# untitled.net
KiCad netlist of a schematic drawn in EAGLE
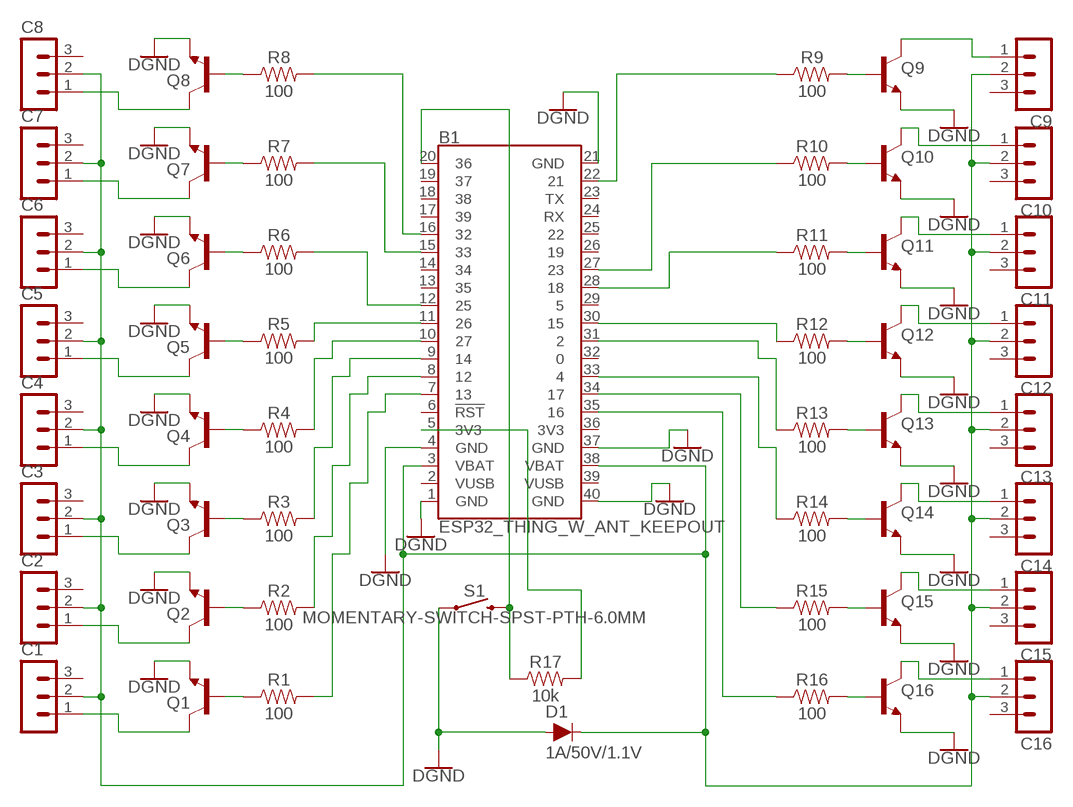
[diagram p0: schematic, sheet 1]

(export (version "E")
  (design (tool "Eeschema 10.0.6"))
  (components
    (comp (ref "B1")
      (value "ESP32_THING_W_ANT_KEEPOUT")
      (footprint "eagle-import:ESP32_THING")
      (libsource (lib "eagle-import") (part "ESP32_THING_W_ANT_KEEPOUT"))
    )
    (comp (ref "C1")
      (value "MA03-1")
      (footprint "eagle-import:MA03-1")
      (libsource (lib "eagle-import") (part "MA03-1"))
    )
    (comp (ref "C2")
      (value "MA03-1")
      (footprint "eagle-import:MA03-1")
      (libsource (lib "eagle-import") (part "MA03-1"))
    )
    (comp (ref "C3")
      (value "MA03-1")
      (footprint "eagle-import:MA03-1")
      (libsource (lib "eagle-import") (part "MA03-1"))
    )
    (comp (ref "C4")
      (value "MA03-1")
      (footprint "eagle-import:MA03-1")
      (libsource (lib "eagle-import") (part "MA03-1"))
    )
    (comp (ref "C5")
      (value "MA03-1")
      (footprint "eagle-import:MA03-1")
      (libsource (lib "eagle-import") (part "MA03-1"))
    )
    (comp (ref "C6")
      (value "MA03-1")
      (footprint "eagle-import:MA03-1")
      (libsource (lib "eagle-import") (part "MA03-1"))
    )
    (comp (ref "C7")
      (value "MA03-1")
      (footprint "eagle-import:MA03-1")
      (libsource (lib "eagle-import") (part "MA03-1"))
    )
    (comp (ref "C8")
      (value "MA03-1")
      (footprint "eagle-import:MA03-1")
      (libsource (lib "eagle-import") (part "MA03-1"))
    )
    (comp (ref "C9")
      (value "MA03-1")
      (footprint "eagle-import:MA03-1")
      (libsource (lib "eagle-import") (part "MA03-1"))
    )
    (comp (ref "C10")
      (value "MA03-1")
      (footprint "eagle-import:MA03-1")
      (libsource (lib "eagle-import") (part "MA03-1"))
    )
    (comp (ref "C11")
      (value "MA03-1")
      (footprint "eagle-import:MA03-1")
      (libsource (lib "eagle-import") (part "MA03-1"))
    )
    (comp (ref "C12")
      (value "MA03-1")
      (footprint "eagle-import:MA03-1")
      (libsource (lib "eagle-import") (part "MA03-1"))
    )
    (comp (ref "C13")
      (value "MA03-1")
      (footprint "eagle-import:MA03-1")
      (libsource (lib "eagle-import") (part "MA03-1"))
    )
    (comp (ref "C14")
      (value "MA03-1")
      (footprint "eagle-import:MA03-1")
      (libsource (lib "eagle-import") (part "MA03-1"))
    )
    (comp (ref "C15")
      (value "MA03-1")
      (footprint "eagle-import:MA03-1")
      (libsource (lib "eagle-import") (part "MA03-1"))
    )
    (comp (ref "C16")
      (value "MA03-1")
      (footprint "eagle-import:MA03-1")
      (libsource (lib "eagle-import") (part "MA03-1"))
    )
    (comp (ref "D1")
      (value "1A/50V/1.1V")
      (footprint "eagle-import:DIODE-1N4001")
      (libsource (lib "eagle-import") (part "DIODE-PTH"))
    )
    (comp (ref "Q1")
      (value "600mA/40V")
      (footprint "eagle-import:TO92-EBC")
      (libsource (lib "eagle-import") (part "-NPN-TO92-EBC2N2222"))
    )
    (comp (ref "Q2")
      (value "600mA/40V")
      (footprint "eagle-import:TO92-EBC")
      (libsource (lib "eagle-import") (part "-NPN-TO92-EBC2N2222"))
    )
    (comp (ref "Q3")
      (value "600mA/40V")
      (footprint "eagle-import:TO92-EBC")
      (libsource (lib "eagle-import") (part "-NPN-TO92-EBC2N2222"))
    )
    (comp (ref "Q4")
      (value "600mA/40V")
      (footprint "eagle-import:TO92-EBC")
      (libsource (lib "eagle-import") (part "-NPN-TO92-EBC2N2222"))
    )
    (comp (ref "Q5")
      (value "600mA/40V")
      (footprint "eagle-import:TO92-EBC")
      (libsource (lib "eagle-import") (part "-NPN-TO92-EBC2N2222"))
    )
    (comp (ref "Q6")
      (value "600mA/40V")
      (footprint "eagle-import:TO92-EBC")
      (libsource (lib "eagle-import") (part "-NPN-TO92-EBC2N2222"))
    )
    (comp (ref "Q7")
      (value "600mA/40V")
      (footprint "eagle-import:TO92-EBC")
      (libsource (lib "eagle-import") (part "-NPN-TO92-EBC2N2222"))
    )
    (comp (ref "Q8")
      (value "600mA/40V")
      (footprint "eagle-import:TO92-EBC")
      (libsource (lib "eagle-import") (part "-NPN-TO92-EBC2N2222"))
    )
    (comp (ref "Q9")
      (value "600mA/40V")
      (footprint "eagle-import:TO92-EBC")
      (libsource (lib "eagle-import") (part "-NPN-TO92-EBC2N2222"))
    )
    (comp (ref "Q10")
      (value "600mA/40V")
      (footprint "eagle-import:TO92-EBC")
      (libsource (lib "eagle-import") (part "-NPN-TO92-EBC2N2222"))
    )
    (comp (ref "Q11")
      (value "600mA/40V")
      (footprint "eagle-import:TO92-EBC")
      (libsource (lib "eagle-import") (part "-NPN-TO92-EBC2N2222"))
    )
    (comp (ref "Q12")
      (value "600mA/40V")
      (footprint "eagle-import:TO92-EBC")
      (libsource (lib "eagle-import") (part "-NPN-TO92-EBC2N2222"))
    )
    (comp (ref "Q13")
      (value "600mA/40V")
      (footprint "eagle-import:TO92-EBC")
      (libsource (lib "eagle-import") (part "-NPN-TO92-EBC2N2222"))
    )
    (comp (ref "Q14")
      (value "600mA/40V")
      (footprint "eagle-import:TO92-EBC")
      (libsource (lib "eagle-import") (part "-NPN-TO92-EBC2N2222"))
    )
    (comp (ref "Q15")
      (value "600mA/40V")
      (footprint "eagle-import:TO92-EBC")
      (libsource (lib "eagle-import") (part "-NPN-TO92-EBC2N2222"))
    )
    (comp (ref "Q16")
      (value "600mA/40V")
      (footprint "eagle-import:TO92-EBC")
      (libsource (lib "eagle-import") (part "-NPN-TO92-EBC2N2222"))
    )
    (comp (ref "R1")
      (value "100")
      (footprint "eagle-import:AXIAL-0.1")
      (libsource (lib "eagle-import") (part "100OHM-VERT-1/4W-1%"))
    )
    (comp (ref "R2")
      (value "100")
      (footprint "eagle-import:AXIAL-0.1")
      (libsource (lib "eagle-import") (part "100OHM-VERT-1/4W-1%"))
    )
    (comp (ref "R3")
      (value "100")
      (footprint "eagle-import:AXIAL-0.1")
      (libsource (lib "eagle-import") (part "100OHM-VERT-1/4W-1%"))
    )
    (comp (ref "R4")
      (value "100")
      (footprint "eagle-import:AXIAL-0.1")
      (libsource (lib "eagle-import") (part "100OHM-VERT-1/4W-1%"))
    )
    (comp (ref "R5")
      (value "100")
      (footprint "eagle-import:AXIAL-0.1")
      (libsource (lib "eagle-import") (part "100OHM-VERT-1/4W-1%"))
    )
    (comp (ref "R6")
      (value "100")
      (footprint "eagle-import:AXIAL-0.1")
      (libsource (lib "eagle-import") (part "100OHM-VERT-1/4W-1%"))
    )
    (comp (ref "R7")
      (value "100")
      (footprint "eagle-import:AXIAL-0.1")
      (libsource (lib "eagle-import") (part "100OHM-VERT-1/4W-1%"))
    )
    (comp (ref "R8")
      (value "100")
      (footprint "eagle-import:AXIAL-0.1")
      (libsource (lib "eagle-import") (part "100OHM-VERT-1/4W-1%"))
    )
    (comp (ref "R9")
      (value "100")
      (footprint "eagle-import:AXIAL-0.1")
      (libsource (lib "eagle-import") (part "100OHM-VERT-1/4W-1%"))
    )
    (comp (ref "R10")
      (value "100")
      (footprint "eagle-import:AXIAL-0.1")
      (libsource (lib "eagle-import") (part "100OHM-VERT-1/4W-1%"))
    )
    (comp (ref "R11")
      (value "100")
      (footprint "eagle-import:AXIAL-0.1")
      (libsource (lib "eagle-import") (part "100OHM-VERT-1/4W-1%"))
    )
    (comp (ref "R12")
      (value "100")
      (footprint "eagle-import:AXIAL-0.1")
      (libsource (lib "eagle-import") (part "100OHM-VERT-1/4W-1%"))
    )
    (comp (ref "R13")
      (value "100")
      (footprint "eagle-import:AXIAL-0.1")
      (libsource (lib "eagle-import") (part "100OHM-VERT-1/4W-1%"))
    )
    (comp (ref "R14")
      (value "100")
      (footprint "eagle-import:AXIAL-0.1")
      (libsource (lib "eagle-import") (part "100OHM-VERT-1/4W-1%"))
    )
    (comp (ref "R15")
      (value "100")
      (footprint "eagle-import:AXIAL-0.1")
      (libsource (lib "eagle-import") (part "100OHM-VERT-1/4W-1%"))
    )
    (comp (ref "R16")
      (value "100")
      (footprint "eagle-import:AXIAL-0.1")
      (libsource (lib "eagle-import") (part "100OHM-VERT-1/4W-1%"))
    )
    (comp (ref "R17")
      (value "10k")
      (footprint "eagle-import:AXIAL-0.1")
      (libsource (lib "eagle-import") (part "10KOHM-VERT-1/4W-5%"))
    )
    (comp (ref "S1")
      (value "MOMENTARY-SWITCH-SPST-PTH-6.0MM")
      (footprint "eagle-import:TACTILE_SWITCH_PTH_6.0MM")
      (libsource (lib "eagle-import") (part "MOMENTARY-SWITCH-SPST-PTH-6.0MM"))
    )
  )
  (nets
    (net (code "1") (name "DGND") (class "Default")
      (node (ref "B1") (pin "1") (pinfunction "GND_1") (pintype "bidirectional"))
      (node (ref "B1") (pin "21") (pinfunction "GND_21") (pintype "bidirectional"))
      (node (ref "B1") (pin "37") (pinfunction "GND_37") (pintype "bidirectional"))
      (node (ref "B1") (pin "4") (pinfunction "GND_4") (pintype "bidirectional"))
      (node (ref "B1") (pin "40") (pinfunction "GND_40") (pintype "bidirectional"))
      (node (ref "D1") (pin "A") (pinfunction "A_A") (pintype "passive"))
      (node (ref "Q1") (pin "E") (pinfunction "E_E") (pintype "passive"))
      (node (ref "Q10") (pin "E") (pinfunction "E_E") (pintype "passive"))
      (node (ref "Q11") (pin "E") (pinfunction "E_E") (pintype "passive"))
      (node (ref "Q12") (pin "E") (pinfunction "E_E") (pintype "passive"))
      (node (ref "Q13") (pin "E") (pinfunction "E_E") (pintype "passive"))
      (node (ref "Q14") (pin "E") (pinfunction "E_E") (pintype "passive"))
      (node (ref "Q15") (pin "E") (pinfunction "E_E") (pintype "passive"))
      (node (ref "Q16") (pin "E") (pinfunction "E_E") (pintype "passive"))
      (node (ref "Q2") (pin "E") (pinfunction "E_E") (pintype "passive"))
      (node (ref "Q3") (pin "E") (pinfunction "E_E") (pintype "passive"))
      (node (ref "Q4") (pin "E") (pinfunction "E_E") (pintype "passive"))
      (node (ref "Q5") (pin "E") (pinfunction "E_E") (pintype "passive"))
      (node (ref "Q6") (pin "E") (pinfunction "E_E") (pintype "passive"))
      (node (ref "Q7") (pin "E") (pinfunction "E_E") (pintype "passive"))
      (node (ref "Q8") (pin "E") (pinfunction "E_E") (pintype "passive"))
      (node (ref "Q9") (pin "E") (pinfunction "E_E") (pintype "passive"))
      (node (ref "S1") (pin "1") (pinfunction "1_1") (pintype "passive"))
    )
    (net (code "2") (name "Net-(B1-2)") (class "Default")
      (node (ref "B1") (pin "31") (pinfunction "2_31") (pintype "bidirectional"))
      (node (ref "R13") (pin "P$1") (pinfunction "1_P$1") (pintype "passive"))
    )
    (net (code "3") (name "Net-(B1-4)") (class "Default")
      (node (ref "B1") (pin "33") (pinfunction "4_33") (pintype "bidirectional"))
      (node (ref "R14") (pin "P$1") (pinfunction "1_P$1") (pintype "passive"))
    )
    (net (code "4") (name "Net-(B1-12)") (class "Default")
      (node (ref "B1") (pin "8") (pinfunction "12_8") (pintype "bidirectional"))
      (node (ref "R2") (pin "P$2") (pinfunction "2_P$2") (pintype "passive"))
    )
    (net (code "5") (name "Net-(B1-13)") (class "Default")
      (node (ref "B1") (pin "7") (pinfunction "13_7") (pintype "bidirectional"))
      (node (ref "R1") (pin "P$2") (pinfunction "2_P$2") (pintype "passive"))
    )
    (net (code "6") (name "Net-(B1-14)") (class "Default")
      (node (ref "B1") (pin "9") (pinfunction "14_9") (pintype "bidirectional"))
      (node (ref "R3") (pin "P$2") (pinfunction "2_P$2") (pintype "passive"))
    )
    (net (code "7") (name "Net-(B1-15)") (class "Default")
      (node (ref "B1") (pin "30") (pinfunction "15_30") (pintype "bidirectional"))
      (node (ref "R12") (pin "P$1") (pinfunction "1_P$1") (pintype "passive"))
    )
    (net (code "8") (name "Net-(B1-16)") (class "Default")
      (node (ref "B1") (pin "35") (pinfunction "16_35") (pintype "bidirectional"))
      (node (ref "R16") (pin "P$1") (pinfunction "1_P$1") (pintype "passive"))
    )
    (net (code "9") (name "Net-(B1-17)") (class "Default")
      (node (ref "B1") (pin "34") (pinfunction "17_34") (pintype "bidirectional"))
      (node (ref "R15") (pin "P$1") (pinfunction "1_P$1") (pintype "passive"))
    )
    (net (code "10") (name "Net-(B1-18)") (class "Default")
      (node (ref "B1") (pin "28") (pinfunction "18_28") (pintype "bidirectional"))
      (node (ref "R11") (pin "P$1") (pinfunction "1_P$1") (pintype "passive"))
    )
    (net (code "11") (name "Net-(B1-21)") (class "Default")
      (node (ref "B1") (pin "22") (pinfunction "21_22") (pintype "bidirectional"))
      (node (ref "R9") (pin "P$1") (pinfunction "1_P$1") (pintype "passive"))
    )
    (net (code "12") (name "Net-(B1-23)") (class "Default")
      (node (ref "B1") (pin "27") (pinfunction "23_27") (pintype "bidirectional"))
      (node (ref "R10") (pin "P$1") (pinfunction "1_P$1") (pintype "passive"))
    )
    (net (code "13") (name "Net-(B1-25)") (class "Default")
      (node (ref "B1") (pin "12") (pinfunction "25_12") (pintype "bidirectional"))
      (node (ref "R6") (pin "P$2") (pinfunction "2_P$2") (pintype "passive"))
    )
    (net (code "14") (name "Net-(B1-26)") (class "Default")
      (node (ref "B1") (pin "11") (pinfunction "26_11") (pintype "bidirectional"))
      (node (ref "R5") (pin "P$2") (pinfunction "2_P$2") (pintype "passive"))
    )
    (net (code "15") (name "Net-(B1-27)") (class "Default")
      (node (ref "B1") (pin "10") (pinfunction "27_10") (pintype "bidirectional"))
      (node (ref "R4") (pin "P$2") (pinfunction "2_P$2") (pintype "passive"))
    )
    (net (code "16") (name "Net-(B1-32)") (class "Default")
      (node (ref "B1") (pin "16") (pinfunction "32_16") (pintype "bidirectional"))
      (node (ref "R8") (pin "P$2") (pinfunction "2_P$2") (pintype "passive"))
    )
    (net (code "17") (name "Net-(B1-33)") (class "Default")
      (node (ref "B1") (pin "15") (pinfunction "33_15") (pintype "bidirectional"))
      (node (ref "R7") (pin "P$2") (pinfunction "2_P$2") (pintype "passive"))
    )
    (net (code "18") (name "Net-(B1-36)") (class "Default")
      (node (ref "B1") (pin "20") (pinfunction "36_20") (pintype "bidirectional"))
      (node (ref "R17") (pin "P$1") (pinfunction "1_P$1") (pintype "passive"))
      (node (ref "S1") (pin "3") (pinfunction "2_3") (pintype "passive"))
    )
    (net (code "19") (name "Net-(B1-VBAT-Pad3)") (class "Default")
      (node (ref "B1") (pin "3") (pinfunction "VBAT_3") (pintype "bidirectional"))
      (node (ref "B1") (pin "38") (pinfunction "VBAT_38") (pintype "bidirectional"))
      (node (ref "C1") (pin "2") (pinfunction "2_2") (pintype "passive"))
      (node (ref "C10") (pin "2") (pinfunction "2_2") (pintype "passive"))
      (node (ref "C11") (pin "2") (pinfunction "2_2") (pintype "passive"))
      (node (ref "C12") (pin "2") (pinfunction "2_2") (pintype "passive"))
      (node (ref "C13") (pin "2") (pinfunction "2_2") (pintype "passive"))
      (node (ref "C14") (pin "2") (pinfunction "2_2") (pintype "passive"))
      (node (ref "C15") (pin "2") (pinfunction "2_2") (pintype "passive"))
      (node (ref "C16") (pin "2") (pinfunction "2_2") (pintype "passive"))
      (node (ref "C2") (pin "2") (pinfunction "2_2") (pintype "passive"))
      (node (ref "C3") (pin "2") (pinfunction "2_2") (pintype "passive"))
      (node (ref "C4") (pin "2") (pinfunction "2_2") (pintype "passive"))
      (node (ref "C5") (pin "2") (pinfunction "2_2") (pintype "passive"))
      (node (ref "C6") (pin "2") (pinfunction "2_2") (pintype "passive"))
      (node (ref "C7") (pin "2") (pinfunction "2_2") (pintype "passive"))
      (node (ref "C8") (pin "2") (pinfunction "2_2") (pintype "passive"))
      (node (ref "C9") (pin "2") (pinfunction "2_2") (pintype "passive"))
      (node (ref "D1") (pin "C") (pinfunction "C_C") (pintype "passive"))
    )
    (net (code "20") (name "Net-(C1-Pad1)") (class "Default")
      (node (ref "C1") (pin "1") (pinfunction "1_1") (pintype "passive"))
      (node (ref "Q1") (pin "C") (pinfunction "C_C") (pintype "passive"))
    )
    (net (code "21") (name "Net-(C2-Pad1)") (class "Default")
      (node (ref "C2") (pin "1") (pinfunction "1_1") (pintype "passive"))
      (node (ref "Q2") (pin "C") (pinfunction "C_C") (pintype "passive"))
    )
    (net (code "22") (name "Net-(C3-Pad1)") (class "Default")
      (node (ref "C3") (pin "1") (pinfunction "1_1") (pintype "passive"))
      (node (ref "Q3") (pin "C") (pinfunction "C_C") (pintype "passive"))
    )
    (net (code "23") (name "Net-(C4-Pad1)") (class "Default")
      (node (ref "C4") (pin "1") (pinfunction "1_1") (pintype "passive"))
      (node (ref "Q4") (pin "C") (pinfunction "C_C") (pintype "passive"))
    )
    (net (code "24") (name "Net-(C5-Pad1)") (class "Default")
      (node (ref "C5") (pin "1") (pinfunction "1_1") (pintype "passive"))
      (node (ref "Q5") (pin "C") (pinfunction "C_C") (pintype "passive"))
    )
    (net (code "25") (name "Net-(C6-Pad1)") (class "Default")
      (node (ref "C6") (pin "1") (pinfunction "1_1") (pintype "passive"))
      (node (ref "Q6") (pin "C") (pinfunction "C_C") (pintype "passive"))
    )
    (net (code "26") (name "Net-(C7-Pad1)") (class "Default")
      (node (ref "C7") (pin "1") (pinfunction "1_1") (pintype "passive"))
      (node (ref "Q7") (pin "C") (pinfunction "C_C") (pintype "passive"))
    )
    (net (code "27") (name "Net-(C8-Pad1)") (class "Default")
      (node (ref "C8") (pin "1") (pinfunction "1_1") (pintype "passive"))
      (node (ref "Q8") (pin "C") (pinfunction "C_C") (pintype "passive"))
    )
    (net (code "28") (name "Net-(C9-Pad1)") (class "Default")
      (node (ref "C9") (pin "1") (pinfunction "1_1") (pintype "passive"))
      (node (ref "Q9") (pin "C") (pinfunction "C_C") (pintype "passive"))
    )
    (net (code "29") (name "Net-(C10-Pad1)") (class "Default")
      (node (ref "C10") (pin "1") (pinfunction "1_1") (pintype "passive"))
      (node (ref "Q10") (pin "C") (pinfunction "C_C") (pintype "passive"))
    )
    (net (code "30") (name "Net-(C11-Pad1)") (class "Default")
      (node (ref "C11") (pin "1") (pinfunction "1_1") (pintype "passive"))
      (node (ref "Q11") (pin "C") (pinfunction "C_C") (pintype "passive"))
    )
    (net (code "31") (name "Net-(C12-Pad1)") (class "Default")
      (node (ref "C12") (pin "1") (pinfunction "1_1") (pintype "passive"))
      (node (ref "Q12") (pin "C") (pinfunction "C_C") (pintype "passive"))
    )
    (net (code "32") (name "Net-(C13-Pad1)") (class "Default")
      (node (ref "C13") (pin "1") (pinfunction "1_1") (pintype "passive"))
      (node (ref "Q13") (pin "C") (pinfunction "C_C") (pintype "passive"))
    )
    (net (code "33") (name "Net-(C14-Pad1)") (class "Default")
      (node (ref "C14") (pin "1") (pinfunction "1_1") (pintype "passive"))
      (node (ref "Q14") (pin "C") (pinfunction "C_C") (pintype "passive"))
    )
    (net (code "34") (name "Net-(C15-Pad1)") (class "Default")
      (node (ref "C15") (pin "1") (pinfunction "1_1") (pintype "passive"))
      (node (ref "Q15") (pin "C") (pinfunction "C_C") (pintype "passive"))
    )
    (net (code "35") (name "Net-(C16-Pad1)") (class "Default")
      (node (ref "C16") (pin "1") (pinfunction "1_1") (pintype "passive"))
      (node (ref "Q16") (pin "C") (pinfunction "C_C") (pintype "passive"))
    )
    (net (code "36") (name "Net-(R1-1)") (class "Default")
      (node (ref "Q1") (pin "B") (pinfunction "B_B") (pintype "passive"))
      (node (ref "R1") (pin "P$1") (pinfunction "1_P$1") (pintype "passive"))
    )
    (net (code "37") (name "Net-(R2-1)") (class "Default")
      (node (ref "Q2") (pin "B") (pinfunction "B_B") (pintype "passive"))
      (node (ref "R2") (pin "P$1") (pinfunction "1_P$1") (pintype "passive"))
    )
    (net (code "38") (name "Net-(R3-1)") (class "Default")
      (node (ref "Q3") (pin "B") (pinfunction "B_B") (pintype "passive"))
      (node (ref "R3") (pin "P$1") (pinfunction "1_P$1") (pintype "passive"))
    )
    (net (code "39") (name "Net-(R4-1)") (class "Default")
      (node (ref "Q4") (pin "B") (pinfunction "B_B") (pintype "passive"))
      (node (ref "R4") (pin "P$1") (pinfunction "1_P$1") (pintype "passive"))
    )
    (net (code "40") (name "Net-(R5-1)") (class "Default")
      (node (ref "Q5") (pin "B") (pinfunction "B_B") (pintype "passive"))
      (node (ref "R5") (pin "P$1") (pinfunction "1_P$1") (pintype "passive"))
    )
    (net (code "41") (name "Net-(R6-1)") (class "Default")
      (node (ref "Q6") (pin "B") (pinfunction "B_B") (pintype "passive"))
      (node (ref "R6") (pin "P$1") (pinfunction "1_P$1") (pintype "passive"))
    )
    (net (code "42") (name "Net-(R7-1)") (class "Default")
      (node (ref "Q7") (pin "B") (pinfunction "B_B") (pintype "passive"))
      (node (ref "R7") (pin "P$1") (pinfunction "1_P$1") (pintype "passive"))
    )
    (net (code "43") (name "Net-(R8-1)") (class "Default")
      (node (ref "Q8") (pin "B") (pinfunction "B_B") (pintype "passive"))
      (node (ref "R8") (pin "P$1") (pinfunction "1_P$1") (pintype "passive"))
    )
    (net (code "44") (name "Net-(R9-2)") (class "Default")
      (node (ref "Q9") (pin "B") (pinfunction "B_B") (pintype "passive"))
      (node (ref "R9") (pin "P$2") (pinfunction "2_P$2") (pintype "passive"))
    )
    (net (code "45") (name "Net-(R10-2)") (class "Default")
      (node (ref "Q10") (pin "B") (pinfunction "B_B") (pintype "passive"))
      (node (ref "R10") (pin "P$2") (pinfunction "2_P$2") (pintype "passive"))
    )
    (net (code "46") (name "Net-(R11-2)") (class "Default")
      (node (ref "Q11") (pin "B") (pinfunction "B_B") (pintype "passive"))
      (node (ref "R11") (pin "P$2") (pinfunction "2_P$2") (pintype "passive"))
    )
    (net (code "47") (name "Net-(R12-2)") (class "Default")
      (node (ref "Q12") (pin "B") (pinfunction "B_B") (pintype "passive"))
      (node (ref "R12") (pin "P$2") (pinfunction "2_P$2") (pintype "passive"))
    )
    (net (code "48") (name "Net-(R13-2)") (class "Default")
      (node (ref "Q13") (pin "B") (pinfunction "B_B") (pintype "passive"))
      (node (ref "R13") (pin "P$2") (pinfunction "2_P$2") (pintype "passive"))
    )
    (net (code "49") (name "Net-(R14-2)") (class "Default")
      (node (ref "Q14") (pin "B") (pinfunction "B_B") (pintype "passive"))
      (node (ref "R14") (pin "P$2") (pinfunction "2_P$2") (pintype "passive"))
    )
    (net (code "50") (name "Net-(R15-2)") (class "Default")
      (node (ref "Q15") (pin "B") (pinfunction "B_B") (pintype "passive"))
      (node (ref "R15") (pin "P$2") (pinfunction "2_P$2") (pintype "passive"))
    )
    (net (code "51") (name "Net-(R16-2)") (class "Default")
      (node (ref "Q16") (pin "B") (pinfunction "B_B") (pintype "passive"))
      (node (ref "R16") (pin "P$2") (pinfunction "2_P$2") (pintype "passive"))
    )
    (net (code "52") (name "Net-(R17-2)") (class "Default")
      (node (ref "B1") (pin "5") (pinfunction "3V3_5") (pintype "bidirectional"))
      (node (ref "R17") (pin "P$2") (pinfunction "2_P$2") (pintype "passive"))
    )
    (net (code "53") (name "unconnected-(B1-0-Pad32)") (class "Default")
      (node (ref "B1") (pin "32") (pinfunction "0_32") (pintype "bidirectional"))
    )
    (net (code "54") (name "unconnected-(B1-3V3-Pad36)") (class "Default")
      (node (ref "B1") (pin "36") (pinfunction "3V3_36") (pintype "bidirectional"))
    )
    (net (code "55") (name "unconnected-(B1-5-Pad29)") (class "Default")
      (node (ref "B1") (pin "29") (pinfunction "5_29") (pintype "bidirectional"))
    )
    (net (code "56") (name "unconnected-(B1-19-Pad26)") (class "Default")
      (node (ref "B1") (pin "26") (pinfunction "19_26") (pintype "bidirectional"))
    )
    (net (code "57") (name "unconnected-(B1-22-Pad25)") (class "Default")
      (node (ref "B1") (pin "25") (pinfunction "22_25") (pintype "bidirectional"))
    )
    (net (code "58") (name "unconnected-(B1-34-Pad14)") (class "Default")
      (node (ref "B1") (pin "14") (pinfunction "34_14") (pintype "bidirectional"))
    )
    (net (code "59") (name "unconnected-(B1-35-Pad13)") (class "Default")
      (node (ref "B1") (pin "13") (pinfunction "35_13") (pintype "bidirectional"))
    )
    (net (code "60") (name "unconnected-(B1-37-Pad19)") (class "Default")
      (node (ref "B1") (pin "19") (pinfunction "37_19") (pintype "bidirectional"))
    )
    (net (code "61") (name "unconnected-(B1-38-Pad18)") (class "Default")
      (node (ref "B1") (pin "18") (pinfunction "38_18") (pintype "bidirectional"))
    )
    (net (code "62") (name "unconnected-(B1-39-Pad17)") (class "Default")
      (node (ref "B1") (pin "17") (pinfunction "39_17") (pintype "bidirectional"))
    )
    (net (code "63") (name "unconnected-(B1-RX-Pad24)") (class "Default")
      (node (ref "B1") (pin "24") (pinfunction "RX_24") (pintype "bidirectional"))
    )
    (net (code "64") (name "unconnected-(B1-TX-Pad23)") (class "Default")
      (node (ref "B1") (pin "23") (pinfunction "TX_23") (pintype "bidirectional"))
    )
    (net (code "65") (name "unconnected-(B1-VUSB-Pad2)") (class "Default")
      (node (ref "B1") (pin "2") (pinfunction "VUSB_2") (pintype "bidirectional"))
    )
    (net (code "66") (name "unconnected-(B1-VUSB-Pad39)") (class "Default")
      (node (ref "B1") (pin "39") (pinfunction "VUSB_39") (pintype "bidirectional"))
    )
    (net (code "67") (name "unconnected-(B1-~{RST}-Pad6)") (class "Default")
      (node (ref "B1") (pin "6") (pinfunction "~{RST}_6") (pintype "bidirectional"))
    )
    (net (code "68") (name "unconnected-(C1-Pad3)") (class "Default")
      (node (ref "C1") (pin "3") (pinfunction "3_3") (pintype "passive"))
    )
    (net (code "69") (name "unconnected-(C2-Pad3)") (class "Default")
      (node (ref "C2") (pin "3") (pinfunction "3_3") (pintype "passive"))
    )
    (net (code "70") (name "unconnected-(C3-Pad3)") (class "Default")
      (node (ref "C3") (pin "3") (pinfunction "3_3") (pintype "passive"))
    )
    (net (code "71") (name "unconnected-(C4-Pad3)") (class "Default")
      (node (ref "C4") (pin "3") (pinfunction "3_3") (pintype "passive"))
    )
    (net (code "72") (name "unconnected-(C5-Pad3)") (class "Default")
      (node (ref "C5") (pin "3") (pinfunction "3_3") (pintype "passive"))
    )
    (net (code "73") (name "unconnected-(C6-Pad3)") (class "Default")
      (node (ref "C6") (pin "3") (pinfunction "3_3") (pintype "passive"))
    )
    (net (code "74") (name "unconnected-(C7-Pad3)") (class "Default")
      (node (ref "C7") (pin "3") (pinfunction "3_3") (pintype "passive"))
    )
    (net (code "75") (name "unconnected-(C8-Pad3)") (class "Default")
      (node (ref "C8") (pin "3") (pinfunction "3_3") (pintype "passive"))
    )
    (net (code "76") (name "unconnected-(C9-Pad3)") (class "Default")
      (node (ref "C9") (pin "3") (pinfunction "3_3") (pintype "passive"))
    )
    (net (code "77") (name "unconnected-(C10-Pad3)") (class "Default")
      (node (ref "C10") (pin "3") (pinfunction "3_3") (pintype "passive"))
    )
    (net (code "78") (name "unconnected-(C11-Pad3)") (class "Default")
      (node (ref "C11") (pin "3") (pinfunction "3_3") (pintype "passive"))
    )
    (net (code "79") (name "unconnected-(C12-Pad3)") (class "Default")
      (node (ref "C12") (pin "3") (pinfunction "3_3") (pintype "passive"))
    )
    (net (code "80") (name "unconnected-(C13-Pad3)") (class "Default")
      (node (ref "C13") (pin "3") (pinfunction "3_3") (pintype "passive"))
    )
    (net (code "81") (name "unconnected-(C14-Pad3)") (class "Default")
      (node (ref "C14") (pin "3") (pinfunction "3_3") (pintype "passive"))
    )
    (net (code "82") (name "unconnected-(C15-Pad3)") (class "Default")
      (node (ref "C15") (pin "3") (pinfunction "3_3") (pintype "passive"))
    )
    (net (code "83") (name "unconnected-(C16-Pad3)") (class "Default")
      (node (ref "C16") (pin "3") (pinfunction "3_3") (pintype "passive"))
    )
  )
)
